# 3xLED_Panel.net
KiCad netlist of a schematic drawn in EAGLE
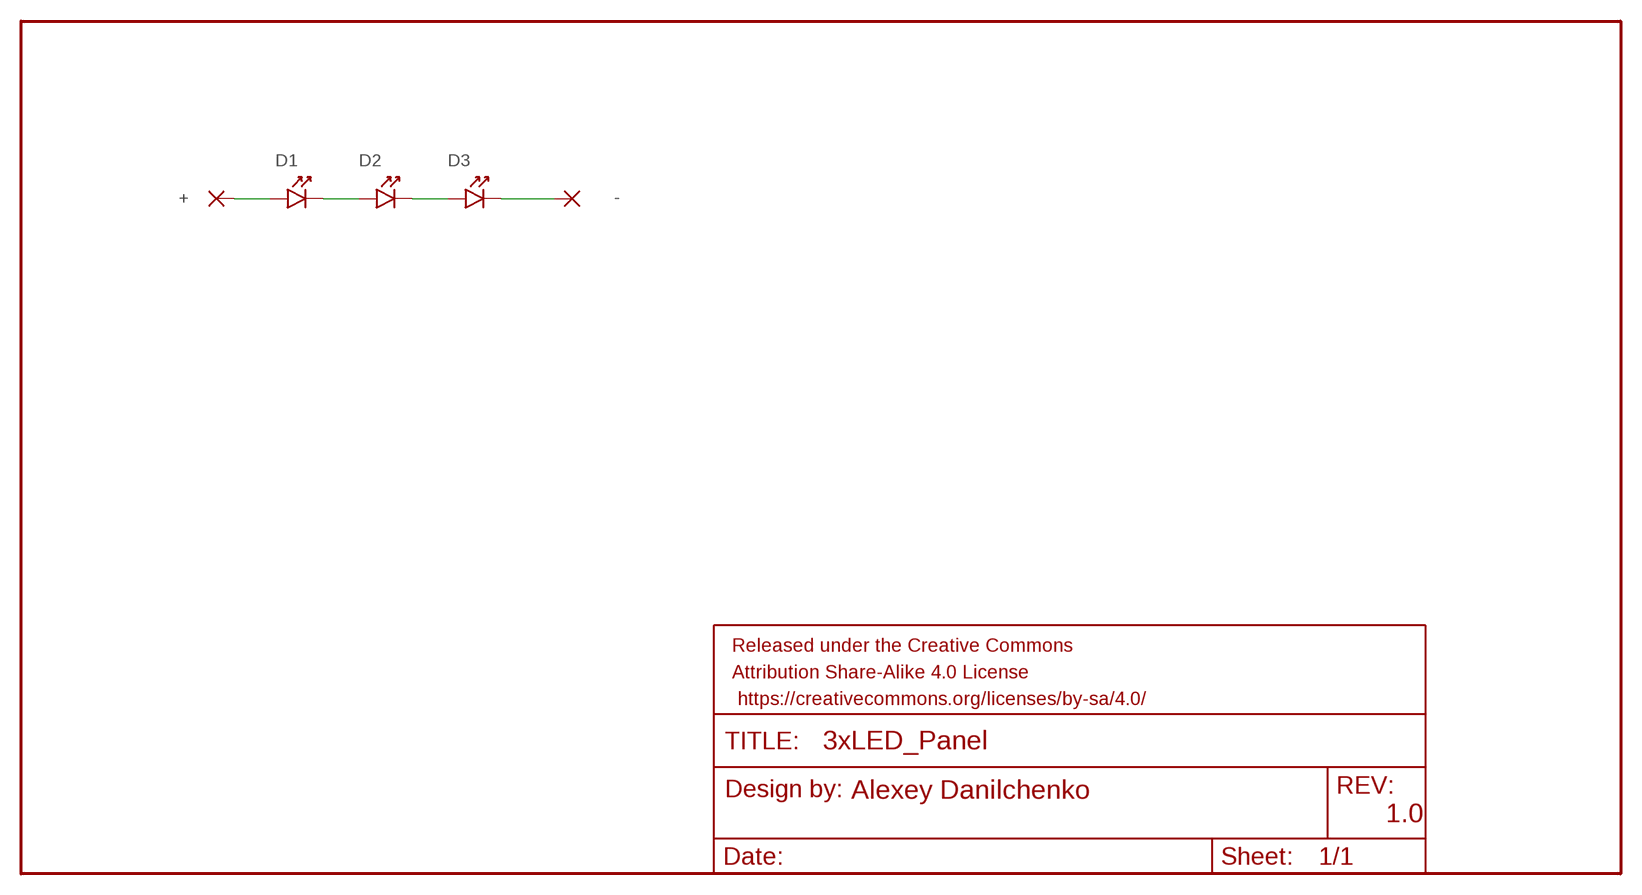
[diagram p0: schematic, sheet 1]

(export (version "E")
  (design (tool "Eeschema 10.0.6"))
  (components
    (comp (ref "+")
      (value "WIREPAD1,6/0,9")
      (footprint "eagle-import:SMD3-2,15")
      (libsource (lib "eagle-import") (part "SMD3X2.15"))
    )
    (comp (ref "-")
      (value "SMD3X2.15")
      (footprint "eagle-import:SMD3-2,15")
      (libsource (lib "eagle-import") (part "SMD3X2.15"))
    )
    (comp (ref "D1")
      (value "YUJI_2835_SMD")
      (footprint "eagle-import:2835_SMD")
      (libsource (lib "eagle-import") (part "YUJI_2835_SMD"))
    )
    (comp (ref "D2")
      (value "YUJI_2835_SMD")
      (footprint "eagle-import:2835_SMD")
      (libsource (lib "eagle-import") (part "YUJI_2835_SMD"))
    )
    (comp (ref "D3")
      (value "YUJI_2835_SMD")
      (footprint "eagle-import:2835_SMD")
      (libsource (lib "eagle-import") (part "YUJI_2835_SMD"))
    )
    (comp (ref "FRAME1")
      (value "FRAME-LEDGER")
      (footprint "eagle-import:CREATIVE_COMMONS")
      (fields (field (name "AUTHOR") "Alexey Danilchenko") (field (name "VER") "1.0"))
      (libsource (lib "eagle-import") (part "FRAME-LEDGER"))
    )
  )
  (nets
    (net (code "1") (name "Net-(+-P)") (class "Default")
      (node (ref "+") (pin "1") (pinfunction "P_1") (pintype "passive"))
      (node (ref "D1") (pin "ANODE") (pinfunction "ANODE_ANODE") (pintype "bidirectional"))
    )
    (net (code "2") (name "Net-(--P)") (class "Default")
      (node (ref "-") (pin "1") (pinfunction "P_1") (pintype "passive"))
      (node (ref "D3") (pin "CATHODE") (pinfunction "CATHODE_CATHODE") (pintype "bidirectional"))
    )
    (net (code "3") (name "Net-(D1-PadCATHODE)") (class "Default")
      (node (ref "D1") (pin "CATHODE") (pinfunction "CATHODE_CATHODE") (pintype "bidirectional"))
      (node (ref "D2") (pin "ANODE") (pinfunction "ANODE_ANODE") (pintype "bidirectional"))
    )
    (net (code "4") (name "Net-(D2-PadCATHODE)") (class "Default")
      (node (ref "D2") (pin "CATHODE") (pinfunction "CATHODE_CATHODE") (pintype "bidirectional"))
      (node (ref "D3") (pin "ANODE") (pinfunction "ANODE_ANODE") (pintype "bidirectional"))
    )
  )
)
